# alimentacao.net
KiCad netlist of a schematic drawn in Altium Designer
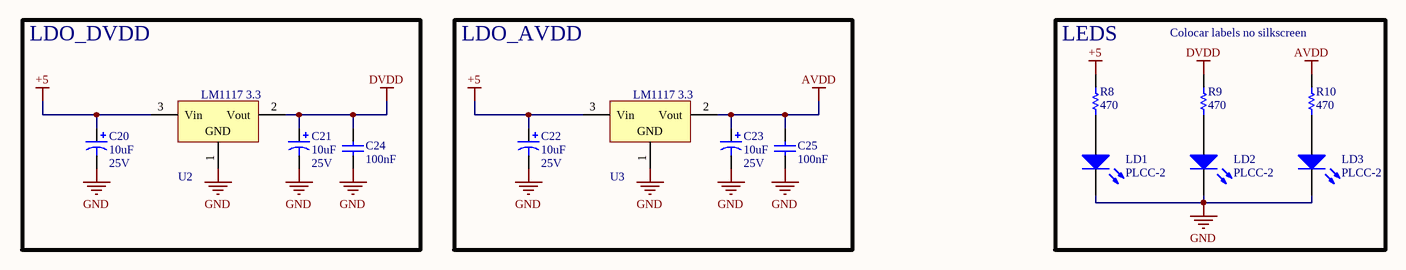
[diagram p0: alimentacao.SchDoc]

(export (version "E")
  (design (tool "Eeschema 10.0.6"))
  (components
    (comp (ref "C20")
      (value "10uF")
      (footprint "CAP2312")
      (fields
        (field (name "TOLERANCE") "20%")
        (field (name "VOLTAGE") "25V")
        (field (name "Comment") "CAP SMD TAN 10UF 25V 2312")
      )
      (libsource (lib "BIB SCH GERAL") (part "CAP SMD TAN 10UF 25V 2312"))
    )
    (comp (ref "C21")
      (value "10uF")
      (footprint "CAP2312")
      (fields
        (field (name "TOLERANCE") "20%")
        (field (name "VOLTAGE") "25V")
        (field (name "Comment") "CAP SMD TAN 10UF 25V 2312")
      )
      (libsource (lib "BIB SCH GERAL") (part "CAP SMD TAN 10UF 25V 2312"))
    )
    (comp (ref "C22")
      (value "10uF")
      (footprint "CAP2312")
      (fields
        (field (name "TOLERANCE") "20%")
        (field (name "VOLTAGE") "25V")
        (field (name "Comment") "CAP SMD TAN 10UF 25V 2312")
      )
      (libsource (lib "BIB SCH GERAL") (part "CAP SMD TAN 10UF 25V 2312"))
    )
    (comp (ref "C23")
      (value "10uF")
      (footprint "CAP2312")
      (fields
        (field (name "TOLERANCE") "20%")
        (field (name "VOLTAGE") "25V")
        (field (name "Comment") "CAP SMD TAN 10UF 25V 2312")
      )
      (libsource (lib "BIB SCH GERAL") (part "CAP SMD TAN 10UF 25V 2312"))
    )
    (comp (ref "C24")
      (value "100nF")
      (footprint "CAP0805OK")
      (fields
        (field (name "TOLERANCE") "10%")
        (field (name "VOLTAGE") "25V")
        (field (name "Comment") "CAP SMD CER 100NF 25V 0805")
      )
      (libsource (lib "BIB SCH GERAL") (part "CAP SMD CER 100NF 25V 0805"))
    )
    (comp (ref "C25")
      (value "100nF")
      (footprint "CAP0805OK")
      (fields
        (field (name "TOLERANCE") "10%")
        (field (name "VOLTAGE") "25V")
        (field (name "Comment") "CAP SMD CER 100NF 25V 0805")
      )
      (libsource (lib "BIB SCH GERAL") (part "CAP SMD CER 100NF 25V 0805"))
    )
    (comp (ref "LD1")
      (value "PLCC-2")
      (footprint "PLCC-2")
      (libsource (lib "BIB SCH GERAL") (part "LED branco /67-21S/KK5C-H6565N32P02833Z6/2T(EMM)/Everlight"))
    )
    (comp (ref "LD2")
      (value "PLCC-2")
      (footprint "PLCC-2")
      (libsource (lib "BIB SCH GERAL") (part "LED branco /67-21S/KK5C-H6565N32P02833Z6/2T(EMM)/Everlight"))
    )
    (comp (ref "LD3")
      (value "PLCC-2")
      (footprint "PLCC-2")
      (libsource (lib "BIB SCH GERAL") (part "LED branco /67-21S/KK5C-H6565N32P02833Z6/2T(EMM)/Everlight"))
    )
    (comp (ref "R8")
      (value "470")
      (footprint "res0805ok")
      (fields (field (name "TOLERANCE") "1%") (field (name "Comment") "RES SMD 1K 1% 0805"))
      (libsource (lib "BIB SCH GERAL") (part "RES SMD 1K 1% 0805"))
    )
    (comp (ref "R9")
      (value "470")
      (footprint "res0805ok")
      (fields (field (name "TOLERANCE") "1%") (field (name "Comment") "RES SMD 1K 1% 0805"))
      (libsource (lib "BIB SCH GERAL") (part "RES SMD 1K 1% 0805"))
    )
    (comp (ref "R10")
      (value "470")
      (footprint "res0805ok")
      (fields (field (name "TOLERANCE") "1%") (field (name "Comment") "RES SMD 1K 1% 0805"))
      (libsource (lib "BIB SCH GERAL") (part "RES SMD 1K 1% 0805"))
    )
    (comp (ref "U2")
      (value "LM1117")
      (footprint "TO252-3")
      (description "800mA Low-Dropout Linear Regulator")
      (fields (field (name "MANUFACTURER") "Texas Instruments") (field (name "VOLTAGE") "1.8 A 5V"))
      (libsource (lib "BIB SCH GERAL") (part "IC SMD REG LM1117 TO252"))
    )
    (comp (ref "U3")
      (value "LM1117")
      (footprint "TO252-3")
      (description "800mA Low-Dropout Linear Regulator")
      (fields (field (name "MANUFACTURER") "Texas Instruments") (field (name "VOLTAGE") "1.8 A 5V"))
      (libsource (lib "BIB SCH GERAL") (part "IC SMD REG LM1117 TO252"))
    )
  )
  (nets
    (net (code "1") (name "+5") (class "Default")
      (node (ref "C20") (pin "1") (pinfunction "1_1") (pintype "passive"))
      (node (ref "C22") (pin "1") (pinfunction "1_1") (pintype "passive"))
      (node (ref "R8") (pin "2") (pinfunction "2_2") (pintype "passive"))
      (node (ref "U2") (pin "3") (pinfunction "Vin_3") (pintype "passive"))
      (node (ref "U3") (pin "3") (pinfunction "Vin_3") (pintype "passive"))
    )
    (net (code "2") (name "AVDD") (class "Default")
      (node (ref "C23") (pin "1") (pinfunction "1_1") (pintype "passive"))
      (node (ref "C25") (pin "1") (pinfunction "1_1") (pintype "passive"))
      (node (ref "R10") (pin "2") (pinfunction "2_2") (pintype "passive"))
      (node (ref "U3") (pin "2") (pinfunction "Vout_2") (pintype "passive"))
    )
    (net (code "3") (name "DVDD") (class "Default")
      (node (ref "C21") (pin "1") (pinfunction "1_1") (pintype "passive"))
      (node (ref "C24") (pin "1") (pinfunction "1_1") (pintype "passive"))
      (node (ref "R9") (pin "2") (pinfunction "2_2") (pintype "passive"))
      (node (ref "U2") (pin "2") (pinfunction "Vout_2") (pintype "passive"))
    )
    (net (code "4") (name "GND") (class "Default")
      (node (ref "C20") (pin "2") (pinfunction "2_2") (pintype "passive"))
      (node (ref "C21") (pin "2") (pinfunction "2_2") (pintype "passive"))
      (node (ref "C22") (pin "2") (pinfunction "2_2") (pintype "passive"))
      (node (ref "C23") (pin "2") (pinfunction "2_2") (pintype "passive"))
      (node (ref "C24") (pin "2") (pinfunction "2_2") (pintype "passive"))
      (node (ref "C25") (pin "2") (pinfunction "2_2") (pintype "passive"))
      (node (ref "LD1") (pin "2") (pinfunction "K_2") (pintype "passive"))
      (node (ref "LD2") (pin "2") (pinfunction "K_2") (pintype "passive"))
      (node (ref "LD3") (pin "2") (pinfunction "K_2") (pintype "passive"))
      (node (ref "U2") (pin "1") (pinfunction "ADJ_1") (pintype "passive"))
      (node (ref "U3") (pin "1") (pinfunction "ADJ_1") (pintype "passive"))
    )
    (net (code "5") (name "Net-(LD1-A)") (class "Default")
      (node (ref "LD1") (pin "1") (pinfunction "A_1") (pintype "passive"))
      (node (ref "R8") (pin "1") (pinfunction "1_1") (pintype "passive"))
    )
    (net (code "6") (name "Net-(LD2-A)") (class "Default")
      (node (ref "LD2") (pin "1") (pinfunction "A_1") (pintype "passive"))
      (node (ref "R9") (pin "1") (pinfunction "1_1") (pintype "passive"))
    )
    (net (code "7") (name "Net-(LD3-A)") (class "Default")
      (node (ref "LD3") (pin "1") (pinfunction "A_1") (pintype "passive"))
      (node (ref "R10") (pin "1") (pinfunction "1_1") (pintype "passive"))
    )
  )
)
